# Output_Isolation.net
KiCad netlist of a schematic drawn in Altium Designer
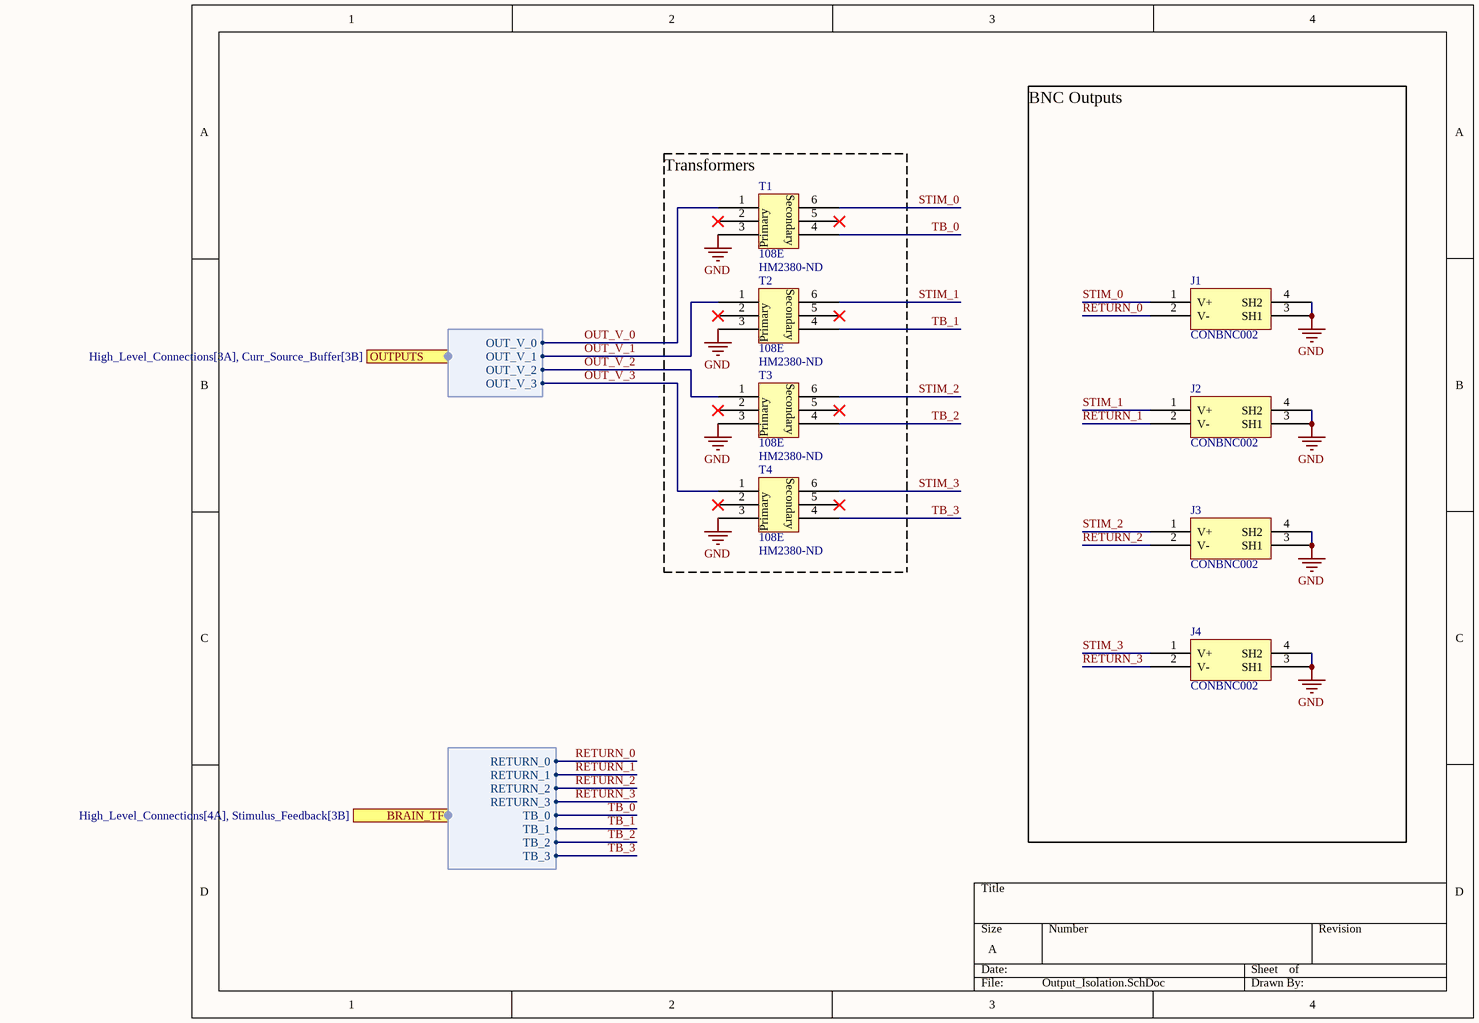
[diagram p0: Output_Isolation.SchDoc]

(export (version "E")
  (design (tool "Eeschema 10.0.6"))
  (components
    (comp (ref "J1")
      (value "BNC Connector")
      (footprint "CONBNC002")
      (fields (field (name "SUPPLIER PART NUMBER 1") "CONBNC002"))
      (libsource (lib "Brain_Stim_Lib") (part "CONBNC002"))
    )
    (comp (ref "J2")
      (value "BNC Connector")
      (footprint "CONBNC002")
      (fields (field (name "SUPPLIER PART NUMBER 1") "CONBNC002"))
      (libsource (lib "Brain_Stim_Lib") (part "CONBNC002"))
    )
    (comp (ref "J3")
      (value "BNC Connector")
      (footprint "CONBNC002")
      (fields (field (name "SUPPLIER PART NUMBER 1") "CONBNC002"))
      (libsource (lib "Brain_Stim_Lib") (part "CONBNC002"))
    )
    (comp (ref "J4")
      (value "BNC Connector")
      (footprint "CONBNC002")
      (fields (field (name "SUPPLIER PART NUMBER 1") "CONBNC002"))
      (libsource (lib "Brain_Stim_Lib") (part "CONBNC002"))
    )
    (comp (ref "T1")
      (value "108E")
      (footprint "108E")
      (fields (field (name "SUPPLIER PART NUMBER 1") "HM2380-ND"))
      (libsource (lib "Brain_Stim_Lib") (part "108E"))
    )
    (comp (ref "T2")
      (value "108E")
      (footprint "108E")
      (fields (field (name "SUPPLIER PART NUMBER 1") "HM2380-ND"))
      (libsource (lib "Brain_Stim_Lib") (part "108E"))
    )
    (comp (ref "T3")
      (value "108E")
      (footprint "108E")
      (fields (field (name "SUPPLIER PART NUMBER 1") "HM2380-ND"))
      (libsource (lib "Brain_Stim_Lib") (part "108E"))
    )
    (comp (ref "T4")
      (value "108E")
      (footprint "108E")
      (fields (field (name "SUPPLIER PART NUMBER 1") "HM2380-ND"))
      (libsource (lib "Brain_Stim_Lib") (part "108E"))
    )
  )
  (nets
    (net (code "3") (name "/OUT_V_0") (class "Default") (node (ref "T1") (pin "1") (pintype "passive")))
    (net (code "4") (name "/OUT_V_1") (class "Default") (node (ref "T2") (pin "1") (pintype "passive")))
    (net (code "5") (name "/OUT_V_2") (class "Default") (node (ref "T3") (pin "1") (pintype "passive")))
    (net (code "6") (name "/OUT_V_3") (class "Default") (node (ref "T4") (pin "1") (pintype "passive")))
    (net (code "7") (name "/RETURN_0") (class "Default")
      (node (ref "J1") (pin "2") (pinfunction "V-_2") (pintype "passive"))
    )
    (net (code "8") (name "/RETURN_1") (class "Default")
      (node (ref "J2") (pin "2") (pinfunction "V-_2") (pintype "passive"))
    )
    (net (code "9") (name "/RETURN_2") (class "Default")
      (node (ref "J3") (pin "2") (pinfunction "V-_2") (pintype "passive"))
    )
    (net (code "10") (name "/RETURN_3") (class "Default")
      (node (ref "J4") (pin "2") (pinfunction "V-_2") (pintype "passive"))
    )
    (net (code "11") (name "/STIM_0") (class "Default")
      (node (ref "J1") (pin "1") (pinfunction "V+_1") (pintype "passive"))
      (node (ref "T1") (pin "6") (pintype "passive"))
    )
    (net (code "12") (name "/STIM_1") (class "Default")
      (node (ref "J2") (pin "1") (pinfunction "V+_1") (pintype "passive"))
      (node (ref "T2") (pin "6") (pintype "passive"))
    )
    (net (code "13") (name "/STIM_2") (class "Default")
      (node (ref "J3") (pin "1") (pinfunction "V+_1") (pintype "passive"))
      (node (ref "T3") (pin "6") (pintype "passive"))
    )
    (net (code "14") (name "/STIM_3") (class "Default")
      (node (ref "J4") (pin "1") (pinfunction "V+_1") (pintype "passive"))
      (node (ref "T4") (pin "6") (pintype "passive"))
    )
    (net (code "15") (name "/TB_0") (class "Default") (node (ref "T1") (pin "4") (pintype "passive")))
    (net (code "16") (name "/TB_1") (class "Default") (node (ref "T2") (pin "4") (pintype "passive")))
    (net (code "17") (name "/TB_2") (class "Default") (node (ref "T3") (pin "4") (pintype "passive")))
    (net (code "18") (name "/TB_3") (class "Default") (node (ref "T4") (pin "4") (pintype "passive")))
    (net (code "21") (name "GND") (class "Default")
      (node (ref "J1") (pin "3") (pinfunction "SH1_3") (pintype "passive"))
      (node (ref "J1") (pin "4") (pinfunction "SH2_4") (pintype "passive"))
      (node (ref "J2") (pin "3") (pinfunction "SH1_3") (pintype "passive"))
      (node (ref "J2") (pin "4") (pinfunction "SH2_4") (pintype "passive"))
      (node (ref "J3") (pin "3") (pinfunction "SH1_3") (pintype "passive"))
      (node (ref "J3") (pin "4") (pinfunction "SH2_4") (pintype "passive"))
      (node (ref "J4") (pin "3") (pinfunction "SH1_3") (pintype "passive"))
      (node (ref "J4") (pin "4") (pinfunction "SH2_4") (pintype "passive"))
      (node (ref "T1") (pin "3") (pintype "passive"))
      (node (ref "T2") (pin "3") (pintype "passive"))
      (node (ref "T3") (pin "3") (pintype "passive"))
      (node (ref "T4") (pin "3") (pintype "passive"))
    )
    (net (code "22") (name "unconnected-(T1-Pad2)") (class "Default")
      (node (ref "T1") (pin "2") (pintype "passive+no_connect"))
    )
    (net (code "23") (name "unconnected-(T1-Pad5)") (class "Default")
      (node (ref "T1") (pin "5") (pintype "passive+no_connect"))
    )
    (net (code "24") (name "unconnected-(T2-Pad2)") (class "Default")
      (node (ref "T2") (pin "2") (pintype "passive+no_connect"))
    )
    (net (code "25") (name "unconnected-(T2-Pad5)") (class "Default")
      (node (ref "T2") (pin "5") (pintype "passive+no_connect"))
    )
    (net (code "26") (name "unconnected-(T3-Pad2)") (class "Default")
      (node (ref "T3") (pin "2") (pintype "passive+no_connect"))
    )
    (net (code "27") (name "unconnected-(T3-Pad5)") (class "Default")
      (node (ref "T3") (pin "5") (pintype "passive+no_connect"))
    )
    (net (code "28") (name "unconnected-(T4-Pad2)") (class "Default")
      (node (ref "T4") (pin "2") (pintype "passive+no_connect"))
    )
    (net (code "29") (name "unconnected-(T4-Pad5)") (class "Default")
      (node (ref "T4") (pin "5") (pintype "passive+no_connect"))
    )
  )
)
